# LFO.net
KiCad netlist of a schematic drawn in Altium Designer
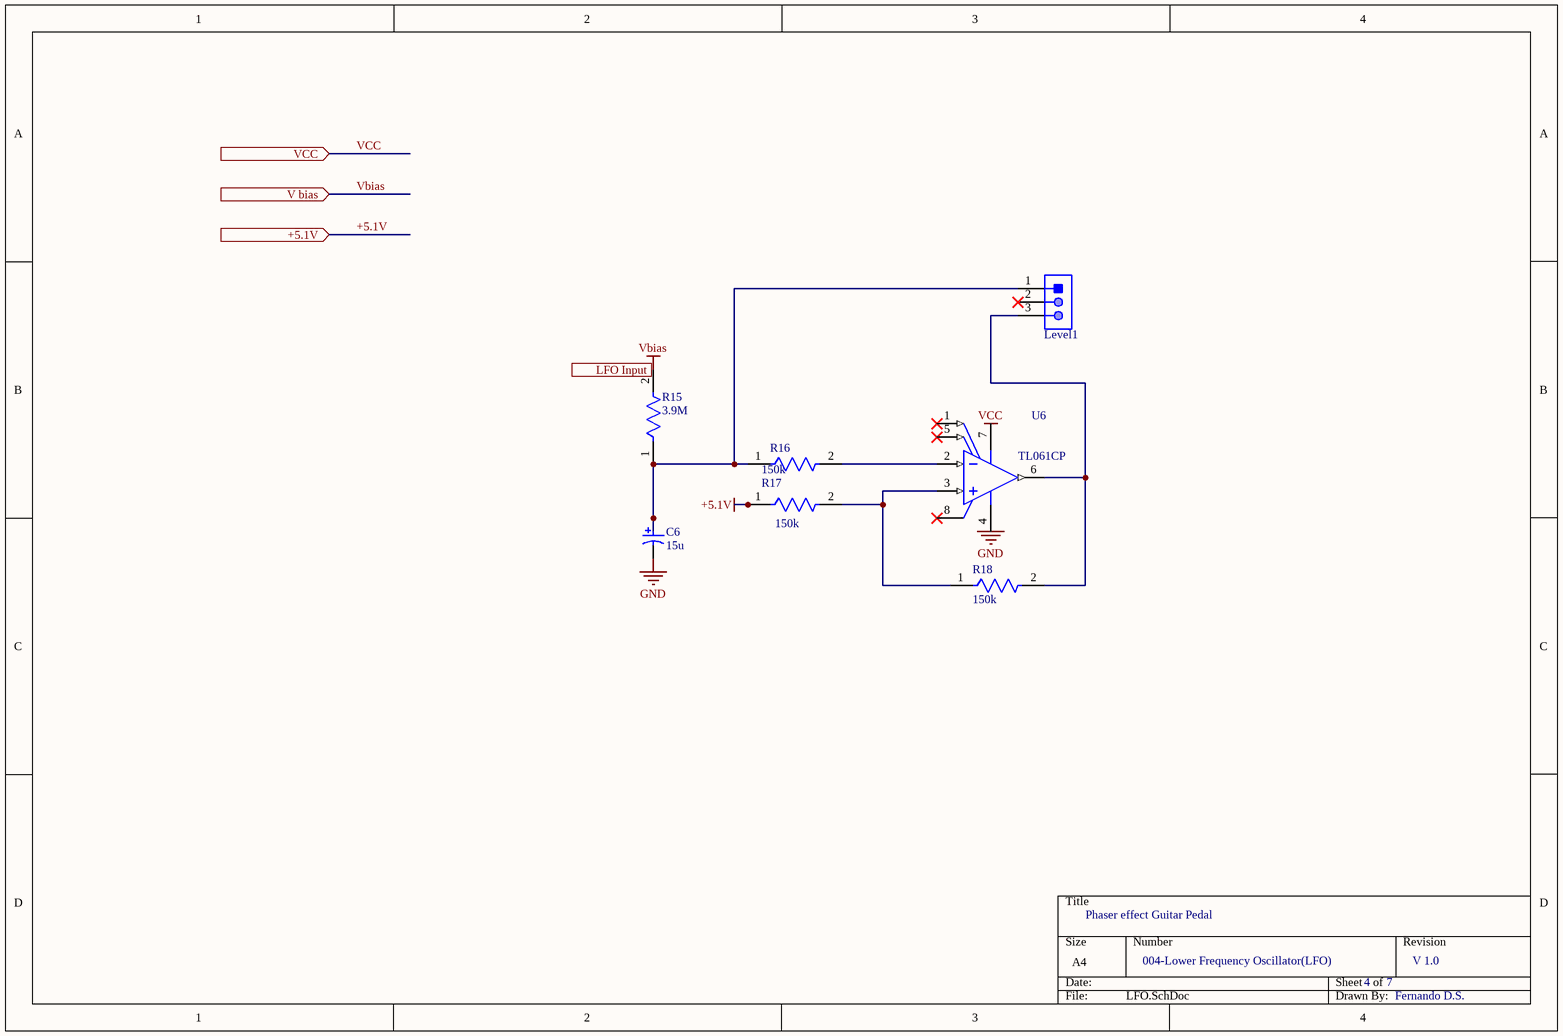
[diagram p0: LFO.SchDoc]

(export (version "E")
  (design (tool "Eeschema 10.0.6"))
  (components
    (comp (ref "C6")
      (value "15u")
      (footprint "NIC-PLF-10x13-2_V")
      (description "Aluminum Electrolytic Capacitor, 470 uF +/-20%, 10 V, -55 to 105 degC, 2-Pin THD, RoHS")
      (fields (field (name "MANUFACTURER") "Nichicon") (field (name "PARTNUMBER") "PLF1A471MDO1"))
      (libsource (lib "Altium Content Vault") (part "NIC-CAP-P-2"))
    )
    (comp (ref "Level1")
      (value "100K")
      (footprint "TECO-171825-3_V")
      (fields (field (name "MANUFACTURER") "TE Connectivity"))
      (libsource (lib "Altium Content Vault") (part "CN-1P-M-R3"))
    )
    (comp (ref "R15")
      (value "3.9M")
      (footprint "FP-MRS25-MFG")
      (fields (field (name "TOLERANCE") "1%"))
      (libsource (lib "Altium Content Vault") (part "1029c3af85768c4190bb7ad29bc67b5"))
    )
    (comp (ref "R16")
      (value "150k")
      (footprint "FP-MRS25-MFG")
      (fields (field (name "TOLERANCE") "1%"))
      (libsource (lib "Altium Content Vault") (part "1029c3af85768c4190bb7ad29bc67b5"))
    )
    (comp (ref "R17")
      (value "150k")
      (footprint "FP-MRS25-MFG")
      (fields (field (name "TOLERANCE") "1%"))
      (libsource (lib "Altium Content Vault") (part "1029c3af85768c4190bb7ad29bc67b5"))
    )
    (comp (ref "R18")
      (value "150k")
      (footprint "FP-MRS25-MFG")
      (fields (field (name "TOLERANCE") "1%"))
      (libsource (lib "Altium Content Vault") (part "1029c3af85768c4190bb7ad29bc67b5"))
    )
    (comp (ref "U6")
      (value "TL061CP")
      (footprint "P0008A")
      (fields (field (name "MANUFACTURER") "Texas Instruments"))
      (libsource (lib "Altium Content Vault") (part "TI-AMP-S5-2-8"))
    )
  )
  (nets
    (net (code "1") (name "+5.1V") (class "Default")
      (node (ref "R17") (pin "1") (pinfunction "1_1") (pintype "passive"))
    )
    (net (code "3") (name "GND") (class "Default")
      (node (ref "C6") (pin "2") (pinfunction "2_2") (pintype "passive"))
    )
    (net (code "4") (name "Net-(C6-Pad1)") (class "Default")
      (node (ref "C6") (pin "1") (pinfunction "1_1") (pintype "passive"))
      (node (ref "Level1") (pin "1") (pinfunction "1_1") (pintype "passive"))
      (node (ref "R15") (pin "1") (pinfunction "1_1") (pintype "passive"))
      (node (ref "R16") (pin "1") (pinfunction "1_1") (pintype "passive"))
    )
    (net (code "5") (name "Net-(U6-IN+)") (class "Default")
      (node (ref "R17") (pin "2") (pinfunction "2_2") (pintype "passive"))
      (node (ref "R18") (pin "1") (pinfunction "1_1") (pintype "passive"))
      (node (ref "U6") (pin "3") (pinfunction "IN+_3") (pintype "input"))
    )
    (net (code "6") (name "Net-(U6-IN-)") (class "Default")
      (node (ref "R16") (pin "2") (pinfunction "2_2") (pintype "passive"))
      (node (ref "U6") (pin "2") (pinfunction "IN-_2") (pintype "input"))
    )
    (net (code "7") (name "Net-(U6-OUT)") (class "Default")
      (node (ref "Level1") (pin "3") (pinfunction "3_3") (pintype "passive"))
      (node (ref "R18") (pin "2") (pinfunction "2_2") (pintype "passive"))
      (node (ref "U6") (pin "6") (pinfunction "OUT_6") (pintype "output"))
    )
    (net (code "9") (name "Vbias") (class "Default")
      (node (ref "R15") (pin "2") (pinfunction "2_2") (pintype "passive"))
    )
    (net (code "10") (name "unconnected-(Level1-Pad2)") (class "Default")
      (node (ref "Level1") (pin "2") (pinfunction "2_2") (pintype "passive+no_connect"))
    )
    (net (code "11") (name "unconnected-(U6-NC-Pad8)") (class "Default")
      (node (ref "U6") (pin "8") (pinfunction "NC_8") (pintype "passive+no_connect"))
    )
    (net (code "12") (name "unconnected-(U6-OFFSET_N1-Pad1)") (class "Default")
      (node (ref "U6") (pin "1") (pinfunction "OFFSET_N1_1") (pintype "input+no_connect"))
    )
    (net (code "13") (name "unconnected-(U6-OFFSET_N2-Pad5)") (class "Default")
      (node (ref "U6") (pin "5") (pinfunction "OFFSET_N2_5") (pintype "input+no_connect"))
    )
    (net (code "14") (name "unconnected-(U6-VCC+-Pad7)") (class "Default")
      (node (ref "U6") (pin "7") (pinfunction "VCC+_7") (pintype "power_in"))
    )
    (net (code "15") (name "unconnected-(U6-VCC--Pad4)") (class "Default")
      (node (ref "U6") (pin "4") (pinfunction "VCC-_4") (pintype "power_in"))
    )
  )
)
